# Rigid-Flex_2_-_PCB_Design.net
KiCad netlist of a schematic drawn in Altium Designer
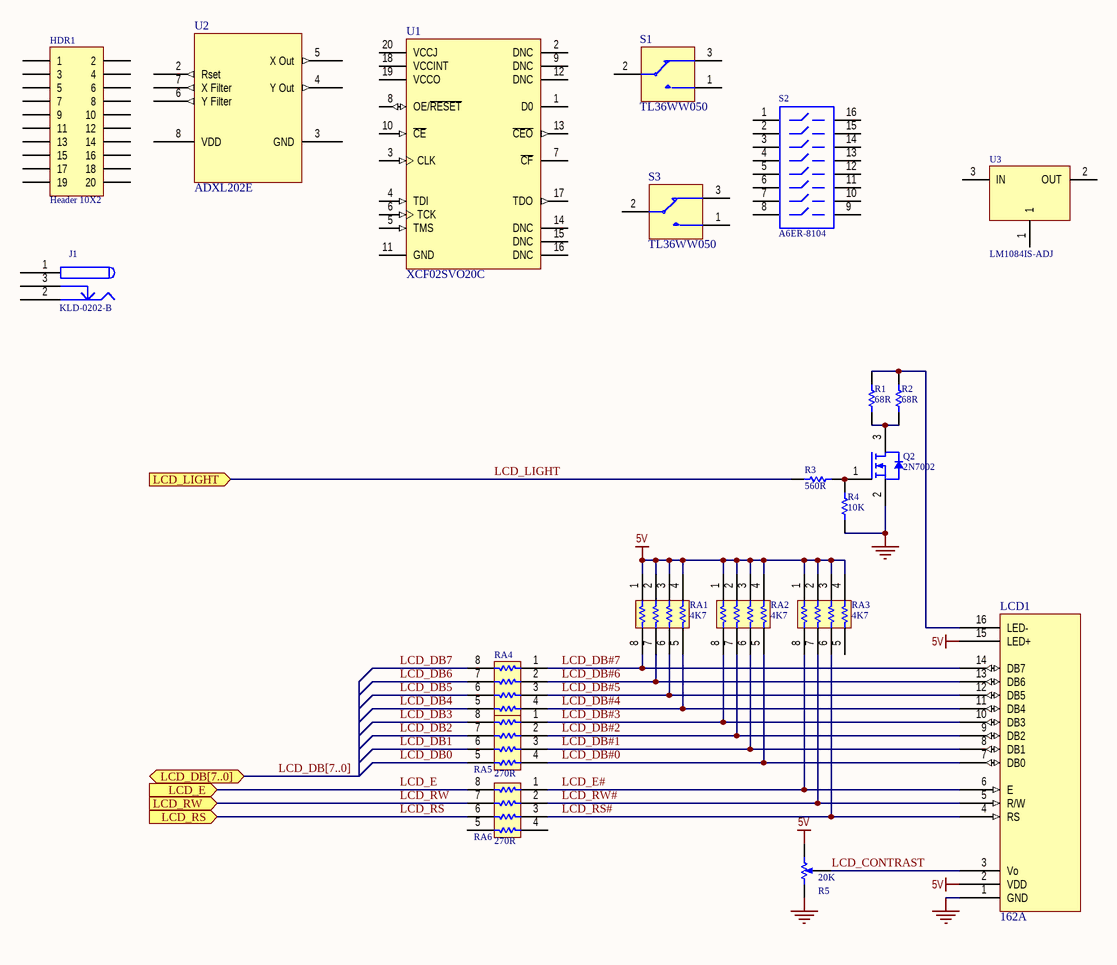
[diagram p0:  Rigid-Flex 2 - PCB Design.SchDoc]

(export (version "E")
  (design (tool "Eeschema 10.0.6"))
  (components
    (comp (ref "HDR1")
      (value "Header 10X2")
      (footprint "HDR2X10")
      (description "Header, 10-Pin, Dual row")
      (libsource (lib "Flex") (part "Header 10X2"))
    )
    (comp (ref "J1")
      (value "KLD-0202-B")
      (footprint "KLD-0202")
      (description "Low Voltage Power Supply Connector")
      (fields (field (name "MANUFACTURER") "Kycon"))
      (libsource (lib "Flex") (part "KLD-0202-B"))
    )
    (comp (ref "LCD1")
      (value "162A")
      (footprint "162A")
      (description "16 char * 2 line LCD character display with b/light")
      (libsource (lib "Flex") (part "162A"))
    )
    (comp (ref "Q2")
      (value "2N7002")
      (footprint "SO-G3")
      (description "N Channel Mosfet")
      (libsource (lib "Flex") (part "2N7002"))
    )
    (comp (ref "R1")
      (value "68R")
      (footprint "CC2012-0805")
      (description "Resistor")
      (libsource (lib "Flex") (part "RES_2"))
    )
    (comp (ref "R2")
      (value "68R")
      (footprint "CC2012-0805")
      (description "Resistor")
      (libsource (lib "Flex") (part "RES_2"))
    )
    (comp (ref "R3")
      (value "560R")
      (footprint "CC2012-0805")
      (description "Resistor")
      (libsource (lib "SpiritLevel_2E") (part "RES"))
    )
    (comp (ref "R4")
      (value "10K")
      (footprint "CR2012-0805")
      (description "Resistor")
      (libsource (lib "Flex") (part "RES"))
    )
    (comp (ref "R5")
      (value "20K")
      (footprint "POT4MM-2")
      (description "Square Trimming Potentiometer")
      (libsource (lib "Flex") (part "RPot SM"))
    )
    (comp (ref "RA1")
      (value "4K7")
      (footprint "MNR34T")
      (description "3216x4 Resistor Array")
      (libsource (lib "Flex") (part "MNR34"))
    )
    (comp (ref "RA2")
      (value "4K7")
      (footprint "MNR34T")
      (description "3216x4 Resistor Array")
      (libsource (lib "Flex") (part "MNR34"))
    )
    (comp (ref "RA3")
      (value "4K7")
      (footprint "MNR34T")
      (description "3216x4 Resistor Array")
      (libsource (lib "Flex") (part "MNR34"))
    )
    (comp (ref "RA4")
      (value "270R")
      (footprint "MNR34")
      (description "3216x4 Resistor Array")
      (libsource (lib "") (part "MNR34_1"))
    )
    (comp (ref "RA5")
      (value "270R")
      (footprint "MNR34")
      (description "3216x4 Resistor Array")
      (libsource (lib "") (part "MNR34_1"))
    )
    (comp (ref "RA6")
      (value "270R")
      (footprint "MNR34")
      (description "3216x4 Resistor Array")
      (libsource (lib "") (part "MNR34_1"))
    )
    (comp (ref "S1")
      (value "TL36WW050")
      (footprint "PCB_SWITCH")
      (description "SPDT Subminiature Toggle Switch")
      (libsource (lib "Flex") (part "PCB_MOUNT_SWITCH"))
    )
    (comp (ref "S2")
      (value "A6ER-8104")
      (footprint "DIP-16-KEY")
      (description "DIP Switch Side actuator long liver Piano Key")
      (libsource (lib "Flex") (part "A6ER-8104"))
    )
    (comp (ref "S3")
      (value "TL36WW050")
      (footprint "PCB_SWITCH")
      (description "SPDT Subminiature Toggle Switch")
      (libsource (lib "Flex") (part "PCB_MOUNT_SWITCH"))
    )
    (comp (ref "U1") (value "XCF02SVO20C") (footprint "VO20") (libsource (lib "Flex") (part "XCF02SVO20C")))
    (comp (ref "U2")
      (value "ADXL202E")
      (footprint "E-8")
      (description "Accelerometer with Digital Output")
      (libsource (lib "Flex") (part "ADXL202E"))
    )
    (comp (ref "U3")
      (value "LM1084IS-ADJ")
      (footprint "TO-263")
      (description "5A Low Dropout Possitive Regulators")
      (libsource (lib "Flex") (part "LM1084IS-ADJ"))
    )
  )
  (nets
    (net (code "1") (name "/LCD_CONTRAST") (class "Default")
      (node (ref "LCD1") (pin "3") (pinfunction "Vo_3") (pintype "tri_state"))
      (node (ref "R5") (pin "W") (pintype "passive"))
    )
    (net (code "2") (name "/LCD_DB#0") (class "Default")
      (node (ref "LCD1") (pin "7") (pinfunction "DB0_7") (pintype "bidirectional"))
      (node (ref "RA2") (pin "5") (pintype "passive"))
      (node (ref "RA5") (pin "4") (pintype "passive"))
    )
    (net (code "3") (name "/LCD_DB#1") (class "Default")
      (node (ref "LCD1") (pin "8") (pinfunction "DB1_8") (pintype "bidirectional"))
      (node (ref "RA2") (pin "6") (pintype "passive"))
      (node (ref "RA5") (pin "3") (pintype "passive"))
    )
    (net (code "4") (name "/LCD_DB#2") (class "Default")
      (node (ref "LCD1") (pin "9") (pinfunction "DB2_9") (pintype "bidirectional"))
      (node (ref "RA2") (pin "7") (pintype "passive"))
      (node (ref "RA5") (pin "2") (pintype "passive"))
    )
    (net (code "5") (name "/LCD_DB#3") (class "Default")
      (node (ref "LCD1") (pin "10") (pinfunction "DB3_10") (pintype "bidirectional"))
      (node (ref "RA2") (pin "8") (pintype "passive"))
      (node (ref "RA5") (pin "1") (pintype "passive"))
    )
    (net (code "6") (name "/LCD_DB#4") (class "Default")
      (node (ref "LCD1") (pin "11") (pinfunction "DB4_11") (pintype "bidirectional"))
      (node (ref "RA1") (pin "5") (pintype "passive"))
      (node (ref "RA4") (pin "4") (pintype "passive"))
    )
    (net (code "7") (name "/LCD_DB#5") (class "Default")
      (node (ref "LCD1") (pin "12") (pinfunction "DB5_12") (pintype "bidirectional"))
      (node (ref "RA1") (pin "6") (pintype "passive"))
      (node (ref "RA4") (pin "3") (pintype "passive"))
    )
    (net (code "8") (name "/LCD_DB#6") (class "Default")
      (node (ref "LCD1") (pin "13") (pinfunction "DB6_13") (pintype "bidirectional"))
      (node (ref "RA1") (pin "7") (pintype "passive"))
      (node (ref "RA4") (pin "2") (pintype "passive"))
    )
    (net (code "9") (name "/LCD_DB#7") (class "Default")
      (node (ref "LCD1") (pin "14") (pinfunction "DB7_14") (pintype "bidirectional"))
      (node (ref "RA1") (pin "8") (pintype "passive"))
      (node (ref "RA4") (pin "1") (pintype "passive"))
    )
    (net (code "10") (name "/LCD_DB0") (class "Default") (node (ref "RA5") (pin "5") (pintype "passive")))
    (net (code "11") (name "/LCD_DB1") (class "Default") (node (ref "RA5") (pin "6") (pintype "passive")))
    (net (code "12") (name "/LCD_DB2") (class "Default") (node (ref "RA5") (pin "7") (pintype "passive")))
    (net (code "13") (name "/LCD_DB3") (class "Default") (node (ref "RA5") (pin "8") (pintype "passive")))
    (net (code "14") (name "/LCD_DB4") (class "Default") (node (ref "RA4") (pin "5") (pintype "passive")))
    (net (code "15") (name "/LCD_DB5") (class "Default") (node (ref "RA4") (pin "6") (pintype "passive")))
    (net (code "16") (name "/LCD_DB6") (class "Default") (node (ref "RA4") (pin "7") (pintype "passive")))
    (net (code "17") (name "/LCD_DB7") (class "Default") (node (ref "RA4") (pin "8") (pintype "passive")))
    (net (code "19") (name "/LCD_E") (class "Default") (node (ref "RA6") (pin "8") (pintype "passive")))
    (net (code "20") (name "/LCD_E#") (class "Default")
      (node (ref "LCD1") (pin "6") (pinfunction "E_6") (pintype "input"))
      (node (ref "RA3") (pin "8") (pintype "passive"))
      (node (ref "RA6") (pin "1") (pintype "passive"))
    )
    (net (code "21") (name "/LCD_LIGHT") (class "Default")
      (node (ref "R3") (pin "1") (pinfunction "1_1") (pintype "passive"))
    )
    (net (code "22") (name "/LCD_RS") (class "Default") (node (ref "RA6") (pin "6") (pintype "passive")))
    (net (code "23") (name "/LCD_RS#") (class "Default")
      (node (ref "LCD1") (pin "4") (pinfunction "RS_4") (pintype "input"))
      (node (ref "RA3") (pin "6") (pintype "passive"))
      (node (ref "RA6") (pin "3") (pintype "passive"))
    )
    (net (code "24") (name "/LCD_RW") (class "Default") (node (ref "RA6") (pin "7") (pintype "passive")))
    (net (code "25") (name "/LCD_RW#") (class "Default")
      (node (ref "LCD1") (pin "5") (pinfunction "R/W_5") (pintype "input"))
      (node (ref "RA3") (pin "7") (pintype "passive"))
      (node (ref "RA6") (pin "2") (pintype "passive"))
    )
    (net (code "26") (name "5V") (class "Default")
      (node (ref "LCD1") (pin "15") (pinfunction "LED+_15") (pintype "power_in"))
      (node (ref "LCD1") (pin "2") (pinfunction "VDD_2") (pintype "power_in"))
      (node (ref "R5") (pin "CW") (pinfunction "+_CW") (pintype "passive"))
      (node (ref "RA1") (pin "1") (pintype "passive"))
      (node (ref "RA1") (pin "2") (pintype "passive"))
      (node (ref "RA1") (pin "3") (pintype "passive"))
      (node (ref "RA1") (pin "4") (pintype "passive"))
      (node (ref "RA2") (pin "1") (pintype "passive"))
      (node (ref "RA2") (pin "2") (pintype "passive"))
      (node (ref "RA2") (pin "3") (pintype "passive"))
      (node (ref "RA2") (pin "4") (pintype "passive"))
      (node (ref "RA3") (pin "1") (pintype "passive"))
      (node (ref "RA3") (pin "2") (pintype "passive"))
      (node (ref "RA3") (pin "3") (pintype "passive"))
      (node (ref "RA3") (pin "4") (pintype "passive"))
    )
    (net (code "27") (name "GND") (class "Default")
      (node (ref "LCD1") (pin "1") (pinfunction "GND_1") (pintype "power_in"))
      (node (ref "Q2") (pin "2") (pintype "passive"))
      (node (ref "R4") (pin "1") (pinfunction "1_1") (pintype "passive"))
      (node (ref "R5") (pin "CCW") (pinfunction "-_CCW") (pintype "passive"))
    )
    (net (code "28") (name "Net-(LCD1-LED-)") (class "Default")
      (node (ref "LCD1") (pin "16") (pinfunction "LED-_16") (pintype "power_in"))
      (node (ref "R1") (pin "1") (pinfunction "1_1") (pintype "passive"))
      (node (ref "R2") (pin "1") (pinfunction "1_1") (pintype "passive"))
    )
    (net (code "29") (name "Net-(Q2-Pad1)") (class "Default")
      (node (ref "Q2") (pin "1") (pintype "passive"))
      (node (ref "R3") (pin "2") (pinfunction "2_2") (pintype "passive"))
      (node (ref "R4") (pin "2") (pinfunction "2_2") (pintype "passive"))
    )
    (net (code "30") (name "Net-(Q2-Pad3)") (class "Default")
      (node (ref "Q2") (pin "3") (pintype "passive"))
      (node (ref "R1") (pin "2") (pinfunction "2_2") (pintype "passive"))
      (node (ref "R2") (pin "2") (pinfunction "2_2") (pintype "passive"))
    )
    (net (code "31") (name "unconnected-(HDR1-Pad1)") (class "Default")
      (node (ref "HDR1") (pin "1") (pinfunction "1_1") (pintype "passive"))
    )
    (net (code "32") (name "unconnected-(HDR1-Pad2)") (class "Default")
      (node (ref "HDR1") (pin "2") (pinfunction "2_2") (pintype "passive"))
    )
    (net (code "33") (name "unconnected-(HDR1-Pad3)") (class "Default")
      (node (ref "HDR1") (pin "3") (pinfunction "3_3") (pintype "passive"))
    )
    (net (code "34") (name "unconnected-(HDR1-Pad4)") (class "Default")
      (node (ref "HDR1") (pin "4") (pinfunction "4_4") (pintype "passive"))
    )
    (net (code "35") (name "unconnected-(HDR1-Pad5)") (class "Default")
      (node (ref "HDR1") (pin "5") (pinfunction "5_5") (pintype "passive"))
    )
    (net (code "36") (name "unconnected-(HDR1-Pad6)") (class "Default")
      (node (ref "HDR1") (pin "6") (pinfunction "6_6") (pintype "passive"))
    )
    (net (code "37") (name "unconnected-(HDR1-Pad7)") (class "Default")
      (node (ref "HDR1") (pin "7") (pinfunction "7_7") (pintype "passive"))
    )
    (net (code "38") (name "unconnected-(HDR1-Pad8)") (class "Default")
      (node (ref "HDR1") (pin "8") (pinfunction "8_8") (pintype "passive"))
    )
    (net (code "39") (name "unconnected-(HDR1-Pad9)") (class "Default")
      (node (ref "HDR1") (pin "9") (pinfunction "9_9") (pintype "passive"))
    )
    (net (code "40") (name "unconnected-(HDR1-Pad10)") (class "Default")
      (node (ref "HDR1") (pin "10") (pinfunction "10_10") (pintype "passive"))
    )
    (net (code "41") (name "unconnected-(HDR1-Pad11)") (class "Default")
      (node (ref "HDR1") (pin "11") (pinfunction "11_11") (pintype "passive"))
    )
    (net (code "42") (name "unconnected-(HDR1-Pad12)") (class "Default")
      (node (ref "HDR1") (pin "12") (pinfunction "12_12") (pintype "passive"))
    )
    (net (code "43") (name "unconnected-(HDR1-Pad13)") (class "Default")
      (node (ref "HDR1") (pin "13") (pinfunction "13_13") (pintype "passive"))
    )
    (net (code "44") (name "unconnected-(HDR1-Pad14)") (class "Default")
      (node (ref "HDR1") (pin "14") (pinfunction "14_14") (pintype "passive"))
    )
    (net (code "45") (name "unconnected-(HDR1-Pad15)") (class "Default")
      (node (ref "HDR1") (pin "15") (pinfunction "15_15") (pintype "passive"))
    )
    (net (code "46") (name "unconnected-(HDR1-Pad16)") (class "Default")
      (node (ref "HDR1") (pin "16") (pinfunction "16_16") (pintype "passive"))
    )
    (net (code "47") (name "unconnected-(HDR1-Pad17)") (class "Default")
      (node (ref "HDR1") (pin "17") (pinfunction "17_17") (pintype "passive"))
    )
    (net (code "48") (name "unconnected-(HDR1-Pad18)") (class "Default")
      (node (ref "HDR1") (pin "18") (pinfunction "18_18") (pintype "passive"))
    )
    (net (code "49") (name "unconnected-(HDR1-Pad19)") (class "Default")
      (node (ref "HDR1") (pin "19") (pinfunction "19_19") (pintype "passive"))
    )
    (net (code "50") (name "unconnected-(HDR1-Pad20)") (class "Default")
      (node (ref "HDR1") (pin "20") (pinfunction "20_20") (pintype "passive"))
    )
    (net (code "51") (name "unconnected-(J1-Pad1)") (class "Default")
      (node (ref "J1") (pin "1") (pintype "power_in"))
    )
    (net (code "52") (name "unconnected-(J1-Pad2)") (class "Default")
      (node (ref "J1") (pin "2") (pintype "power_in"))
    )
    (net (code "53") (name "unconnected-(J1-Pad3)") (class "Default")
      (node (ref "J1") (pin "3") (pintype "power_in"))
    )
    (net (code "54") (name "unconnected-(RA3-Pad5)") (class "Default")
      (node (ref "RA3") (pin "5") (pintype "passive"))
    )
    (net (code "55") (name "unconnected-(RA6-Pad4)") (class "Default")
      (node (ref "RA6") (pin "4") (pintype "passive"))
    )
    (net (code "56") (name "unconnected-(RA6-Pad5)") (class "Default")
      (node (ref "RA6") (pin "5") (pintype "passive"))
    )
    (net (code "57") (name "unconnected-(S1-Pad1)") (class "Default")
      (node (ref "S1") (pin "1") (pintype "passive"))
    )
    (net (code "58") (name "unconnected-(S1-Pad2)") (class "Default")
      (node (ref "S1") (pin "2") (pintype "passive"))
    )
    (net (code "59") (name "unconnected-(S1-Pad3)") (class "Default")
      (node (ref "S1") (pin "3") (pintype "passive"))
    )
    (net (code "60") (name "unconnected-(S2-Pad1)") (class "Default")
      (node (ref "S2") (pin "1") (pinfunction "1_1") (pintype "passive"))
    )
    (net (code "61") (name "unconnected-(S2-Pad2)") (class "Default")
      (node (ref "S2") (pin "2") (pinfunction "2_2") (pintype "passive"))
    )
    (net (code "62") (name "unconnected-(S2-Pad3)") (class "Default")
      (node (ref "S2") (pin "3") (pinfunction "3_3") (pintype "passive"))
    )
    (net (code "63") (name "unconnected-(S2-Pad4)") (class "Default")
      (node (ref "S2") (pin "4") (pinfunction "4_4") (pintype "passive"))
    )
    (net (code "64") (name "unconnected-(S2-Pad5)") (class "Default")
      (node (ref "S2") (pin "5") (pinfunction "5_5") (pintype "passive"))
    )
    (net (code "65") (name "unconnected-(S2-Pad6)") (class "Default")
      (node (ref "S2") (pin "6") (pinfunction "6_6") (pintype "passive"))
    )
    (net (code "66") (name "unconnected-(S2-Pad7)") (class "Default")
      (node (ref "S2") (pin "7") (pinfunction "7_7") (pintype "passive"))
    )
    (net (code "67") (name "unconnected-(S2-Pad8)") (class "Default")
      (node (ref "S2") (pin "8") (pinfunction "8_8") (pintype "passive"))
    )
    (net (code "68") (name "unconnected-(S2-Pad9)") (class "Default")
      (node (ref "S2") (pin "9") (pinfunction "9_9") (pintype "passive"))
    )
    (net (code "69") (name "unconnected-(S2-Pad10)") (class "Default")
      (node (ref "S2") (pin "10") (pinfunction "10_10") (pintype "passive"))
    )
    (net (code "70") (name "unconnected-(S2-Pad11)") (class "Default")
      (node (ref "S2") (pin "11") (pinfunction "11_11") (pintype "passive"))
    )
    (net (code "71") (name "unconnected-(S2-Pad12)") (class "Default")
      (node (ref "S2") (pin "12") (pinfunction "12_12") (pintype "passive"))
    )
    (net (code "72") (name "unconnected-(S2-Pad13)") (class "Default")
      (node (ref "S2") (pin "13") (pinfunction "13_13") (pintype "passive"))
    )
    (net (code "73") (name "unconnected-(S2-Pad14)") (class "Default")
      (node (ref "S2") (pin "14") (pinfunction "14_14") (pintype "passive"))
    )
    (net (code "74") (name "unconnected-(S2-Pad15)") (class "Default")
      (node (ref "S2") (pin "15") (pinfunction "15_15") (pintype "passive"))
    )
    (net (code "75") (name "unconnected-(S2-Pad16)") (class "Default")
      (node (ref "S2") (pin "16") (pinfunction "16_16") (pintype "passive"))
    )
    (net (code "76") (name "unconnected-(S3-Pad1)") (class "Default")
      (node (ref "S3") (pin "1") (pintype "passive"))
    )
    (net (code "77") (name "unconnected-(S3-Pad2)") (class "Default")
      (node (ref "S3") (pin "2") (pintype "passive"))
    )
    (net (code "78") (name "unconnected-(S3-Pad3)") (class "Default")
      (node (ref "S3") (pin "3") (pintype "passive"))
    )
    (net (code "79") (name "unconnected-(U1-CLK-Pad3)") (class "Default")
      (node (ref "U1") (pin "3") (pinfunction "CLK_3") (pintype "input"))
    )
    (net (code "80") (name "unconnected-(U1-D0-Pad1)") (class "Default")
      (node (ref "U1") (pin "1") (pinfunction "D0_1") (pintype "tri_state"))
    )
    (net (code "81") (name "unconnected-(U1-DNC-Pad2)") (class "Default")
      (node (ref "U1") (pin "2") (pinfunction "DNC_2") (pintype "passive"))
    )
    (net (code "82") (name "unconnected-(U1-DNC-Pad9)") (class "Default")
      (node (ref "U1") (pin "9") (pinfunction "DNC_9") (pintype "passive"))
    )
    (net (code "83") (name "unconnected-(U1-DNC-Pad12)") (class "Default")
      (node (ref "U1") (pin "12") (pinfunction "DNC_12") (pintype "passive"))
    )
    (net (code "84") (name "unconnected-(U1-DNC-Pad14)") (class "Default")
      (node (ref "U1") (pin "14") (pinfunction "DNC_14") (pintype "passive"))
    )
    (net (code "85") (name "unconnected-(U1-DNC-Pad15)") (class "Default")
      (node (ref "U1") (pin "15") (pinfunction "DNC_15") (pintype "passive"))
    )
    (net (code "86") (name "unconnected-(U1-DNC-Pad16)") (class "Default")
      (node (ref "U1") (pin "16") (pinfunction "DNC_16") (pintype "passive"))
    )
    (net (code "87") (name "unconnected-(U1-GND-Pad11)") (class "Default")
      (node (ref "U1") (pin "11") (pinfunction "GND_11") (pintype "power_in"))
    )
    (net (code "88") (name "unconnected-(U1-OE{slash}~{RESET}-Pad8)") (class "Default")
      (node (ref "U1") (pin "8") (pinfunction "OE/~{RESET}_8") (pintype "bidirectional"))
    )
    (net (code "89") (name "unconnected-(U1-TCK-Pad6)") (class "Default")
      (node (ref "U1") (pin "6") (pinfunction "TCK_6") (pintype "input"))
    )
    (net (code "90") (name "unconnected-(U1-TDI-Pad4)") (class "Default")
      (node (ref "U1") (pin "4") (pinfunction "TDI_4") (pintype "input"))
    )
    (net (code "91") (name "unconnected-(U1-TDO-Pad17)") (class "Default")
      (node (ref "U1") (pin "17") (pinfunction "TDO_17") (pintype "output"))
    )
    (net (code "92") (name "unconnected-(U1-TMS-Pad5)") (class "Default")
      (node (ref "U1") (pin "5") (pinfunction "TMS_5") (pintype "input"))
    )
    (net (code "93") (name "unconnected-(U1-VCCINT-Pad18)") (class "Default")
      (node (ref "U1") (pin "18") (pinfunction "VCCINT_18") (pintype "power_in"))
    )
    (net (code "94") (name "unconnected-(U1-VCCJ-Pad20)") (class "Default")
      (node (ref "U1") (pin "20") (pinfunction "VCCJ_20") (pintype "power_in"))
    )
    (net (code "95") (name "unconnected-(U1-VCCO-Pad19)") (class "Default")
      (node (ref "U1") (pin "19") (pinfunction "VCCO_19") (pintype "power_in"))
    )
    (net (code "96") (name "unconnected-(U1-~{CEO}-Pad13)") (class "Default")
      (node (ref "U1") (pin "13") (pinfunction "~{CEO}_13") (pintype "output"))
    )
    (net (code "97") (name "unconnected-(U1-~{CE}-Pad10)") (class "Default")
      (node (ref "U1") (pin "10") (pinfunction "~{CE}_10") (pintype "input"))
    )
    (net (code "98") (name "unconnected-(U1-~{CF}-Pad7)") (class "Default")
      (node (ref "U1") (pin "7") (pinfunction "~{CF}_7") (pintype "open_collector"))
    )
    (net (code "99") (name "unconnected-(U2-GND-Pad3)") (class "Default")
      (node (ref "U2") (pin "3") (pinfunction "GND_3") (pintype "power_in"))
    )
    (net (code "100") (name "unconnected-(U2-Rset-Pad2)") (class "Default")
      (node (ref "U2") (pin "2") (pinfunction "Rset_2") (pintype "output"))
    )
    (net (code "101") (name "unconnected-(U2-Self_Test-Pad1)") (class "Default")
      (node (ref "U2") (pin "1") (pinfunction "Self_Test_1") (pintype "input"))
    )
    (net (code "102") (name "unconnected-(U2-VDD-Pad8)") (class "Default")
      (node (ref "U2") (pin "8") (pinfunction "VDD_8") (pintype "power_in"))
    )
    (net (code "103") (name "unconnected-(U2-X_Filter-Pad7)") (class "Default")
      (node (ref "U2") (pin "7") (pinfunction "X_Filter_7") (pintype "output"))
    )
    (net (code "104") (name "unconnected-(U2-X_Out-Pad5)") (class "Default")
      (node (ref "U2") (pin "5") (pinfunction "X_Out_5") (pintype "output"))
    )
    (net (code "105") (name "unconnected-(U2-Y_Filter-Pad6)") (class "Default")
      (node (ref "U2") (pin "6") (pinfunction "Y_Filter_6") (pintype "output"))
    )
    (net (code "106") (name "unconnected-(U2-Y_Out-Pad4)") (class "Default")
      (node (ref "U2") (pin "4") (pinfunction "Y_Out_4") (pintype "output"))
    )
    (net (code "107") (name "unconnected-(U3-IN-Pad3)") (class "Default")
      (node (ref "U3") (pin "3") (pinfunction "IN_3") (pintype "power_in"))
    )
    (net (code "108") (name "unconnected-(U3-OUT-Pad2)") (class "Default")
      (node (ref "U3") (pin "2") (pinfunction "OUT_2") (pintype "power_in"))
    )
    (net (code "109") (name "unconnected-(U3-Pad1)") (class "Default")
      (node (ref "U3") (pin "1") (pinfunction "1_1") (pintype "passive"))
    )
  )
)
